# 02_CONNECTION.net
KiCad netlist of a schematic drawn in Altium Designer
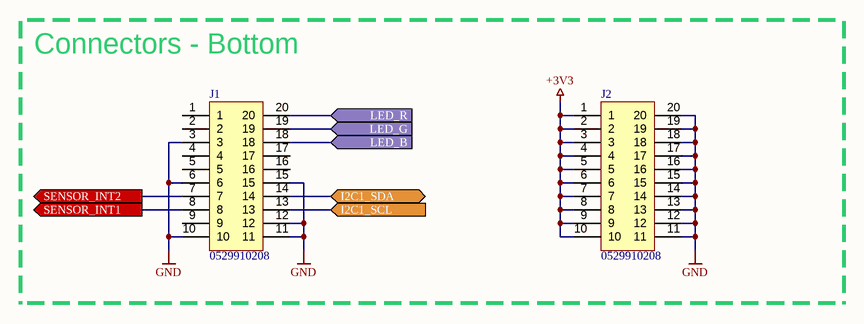
[diagram p0: 02 CONNECTION.SchDoc]

(export (version "E")
  (design (tool "Eeschema 10.0.6"))
  (components
    (comp (ref "J1")
      (value "0529910208")
      (footprint "0529910208")
      (description "CONN PLUG 20POS SMD GOLD")
      (fields (field (name "MANUFACTURER") "MOLEX"))
      (libsource (lib "altium_symbol") (part "0529910208"))
    )
    (comp (ref "J2")
      (value "0529910208")
      (footprint "0529910208")
      (description "CONN PLUG 20POS SMD GOLD")
      (fields (field (name "MANUFACTURER") "MOLEX"))
      (libsource (lib "altium_symbol") (part "0529910208"))
    )
  )
  (nets
    (net (code "1") (name "+3V3") (class "Default")
      (node (ref "J2") (pin "1") (pinfunction "1_1") (pintype "passive"))
      (node (ref "J2") (pin "10") (pinfunction "10_10") (pintype "passive"))
      (node (ref "J2") (pin "2") (pinfunction "2_2") (pintype "passive"))
      (node (ref "J2") (pin "3") (pinfunction "3_3") (pintype "passive"))
      (node (ref "J2") (pin "4") (pinfunction "4_4") (pintype "passive"))
      (node (ref "J2") (pin "5") (pinfunction "5_5") (pintype "passive"))
      (node (ref "J2") (pin "6") (pinfunction "6_6") (pintype "passive"))
      (node (ref "J2") (pin "7") (pinfunction "7_7") (pintype "passive"))
      (node (ref "J2") (pin "8") (pinfunction "8_8") (pintype "passive"))
      (node (ref "J2") (pin "9") (pinfunction "9_9") (pintype "passive"))
    )
    (net (code "2") (name "/I2C1_SCL") (class "Default")
      (node (ref "J1") (pin "13") (pinfunction "13_13") (pintype "passive"))
    )
    (net (code "3") (name "/I2C1_SDA") (class "Default")
      (node (ref "J1") (pin "14") (pinfunction "14_14") (pintype "passive"))
    )
    (net (code "4") (name "/LED_B") (class "Default")
      (node (ref "J1") (pin "18") (pinfunction "18_18") (pintype "passive"))
    )
    (net (code "5") (name "/LED_G") (class "Default")
      (node (ref "J1") (pin "19") (pinfunction "19_19") (pintype "passive"))
    )
    (net (code "6") (name "/LED_R") (class "Default")
      (node (ref "J1") (pin "20") (pinfunction "20_20") (pintype "passive"))
    )
    (net (code "7") (name "/SENSOR_INT1") (class "Default")
      (node (ref "J1") (pin "8") (pinfunction "8_8") (pintype "passive"))
    )
    (net (code "8") (name "/SENSOR_INT2") (class "Default")
      (node (ref "J1") (pin "7") (pinfunction "7_7") (pintype "passive"))
    )
    (net (code "9") (name "GND") (class "Default")
      (node (ref "J1") (pin "10") (pinfunction "10_10") (pintype "passive"))
      (node (ref "J1") (pin "11") (pinfunction "11_11") (pintype "passive"))
      (node (ref "J1") (pin "12") (pinfunction "12_12") (pintype "passive"))
      (node (ref "J1") (pin "15") (pinfunction "15_15") (pintype "passive"))
      (node (ref "J1") (pin "3") (pinfunction "3_3") (pintype "passive"))
      (node (ref "J1") (pin "6") (pinfunction "6_6") (pintype "passive"))
      (node (ref "J2") (pin "11") (pinfunction "11_11") (pintype "passive"))
      (node (ref "J2") (pin "12") (pinfunction "12_12") (pintype "passive"))
      (node (ref "J2") (pin "13") (pinfunction "13_13") (pintype "passive"))
      (node (ref "J2") (pin "14") (pinfunction "14_14") (pintype "passive"))
      (node (ref "J2") (pin "15") (pinfunction "15_15") (pintype "passive"))
      (node (ref "J2") (pin "16") (pinfunction "16_16") (pintype "passive"))
      (node (ref "J2") (pin "17") (pinfunction "17_17") (pintype "passive"))
      (node (ref "J2") (pin "18") (pinfunction "18_18") (pintype "passive"))
      (node (ref "J2") (pin "19") (pinfunction "19_19") (pintype "passive"))
      (node (ref "J2") (pin "20") (pinfunction "20_20") (pintype "passive"))
    )
    (net (code "10") (name "unconnected-(J1-Pad1)") (class "Default")
      (node (ref "J1") (pin "1") (pinfunction "1_1") (pintype "passive"))
    )
    (net (code "11") (name "unconnected-(J1-Pad2)") (class "Default")
      (node (ref "J1") (pin "2") (pinfunction "2_2") (pintype "passive"))
    )
    (net (code "12") (name "unconnected-(J1-Pad4)") (class "Default")
      (node (ref "J1") (pin "4") (pinfunction "4_4") (pintype "passive"))
    )
    (net (code "13") (name "unconnected-(J1-Pad5)") (class "Default")
      (node (ref "J1") (pin "5") (pinfunction "5_5") (pintype "passive"))
    )
    (net (code "14") (name "unconnected-(J1-Pad9)") (class "Default")
      (node (ref "J1") (pin "9") (pinfunction "9_9") (pintype "passive"))
    )
    (net (code "15") (name "unconnected-(J1-Pad16)") (class "Default")
      (node (ref "J1") (pin "16") (pinfunction "16_16") (pintype "passive"))
    )
    (net (code "16") (name "unconnected-(J1-Pad17)") (class "Default")
      (node (ref "J1") (pin "17") (pinfunction "17_17") (pintype "passive"))
    )
  )
)
